# LMP91000_NO2_Sensor.net
KiCad netlist of a schematic drawn in Altium Designer
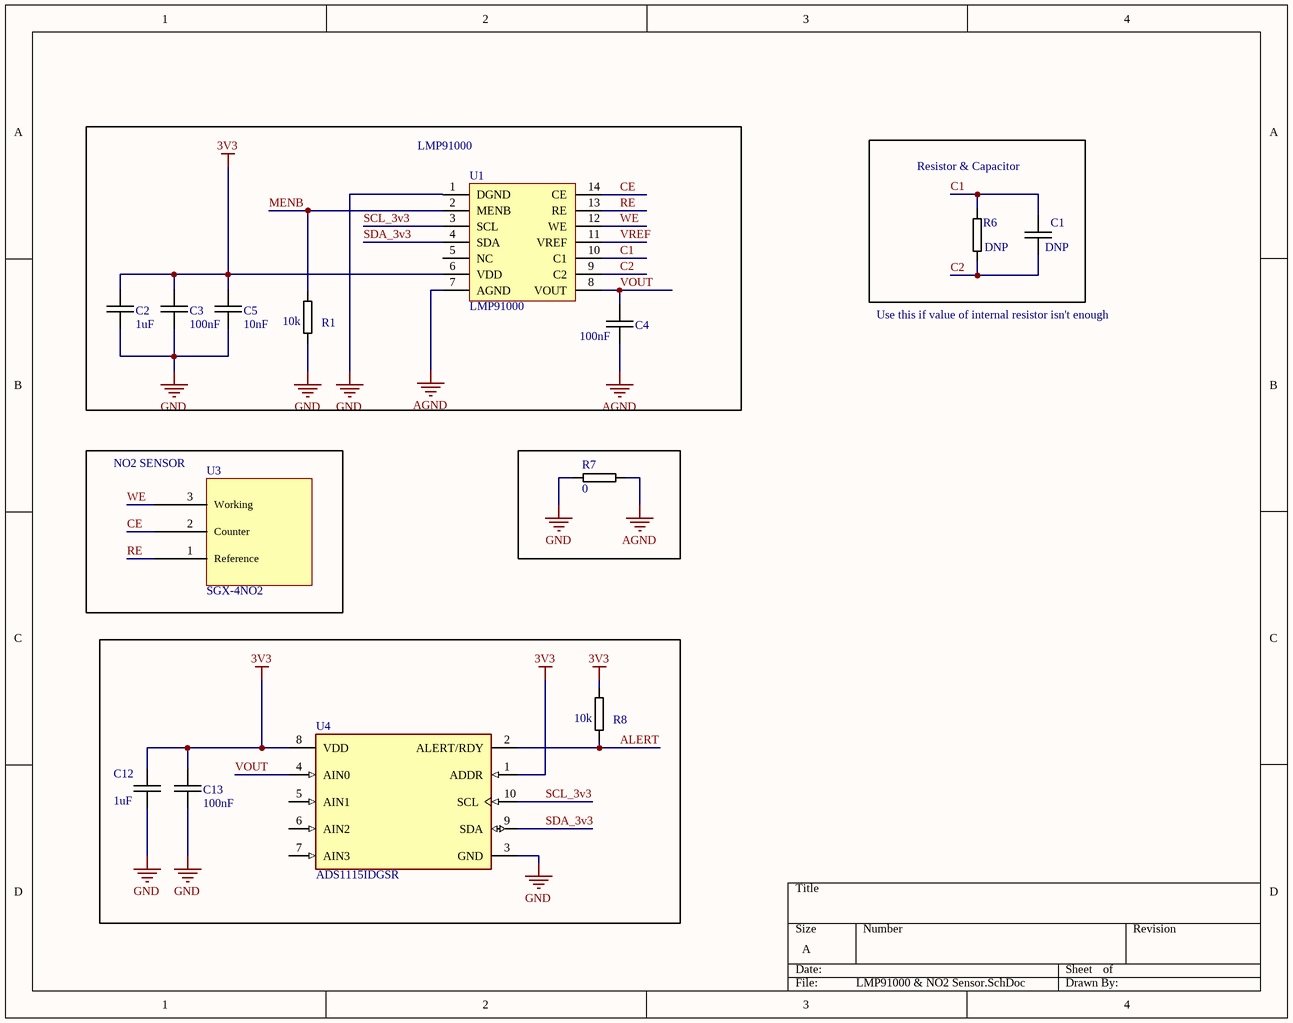
[diagram p0: LMP91000 & NO2 Sensor.SchDoc]

(export (version "E")
  (design (tool "Eeschema 10.0.6"))
  (components
    (comp (ref "C1") (value "DNP") (footprint "0603C") (libsource (lib "TAVU Altium library") (part "0603C")))
    (comp (ref "C2") (value "1uF") (footprint "0603C") (libsource (lib "TAVU Altium library") (part "0603C")))
    (comp (ref "C3")
      (value "100nF")
      (footprint "0603C")
      (libsource (lib "TAVU Altium library") (part "0603C"))
    )
    (comp (ref "C4")
      (value "100nF")
      (footprint "0603C")
      (libsource (lib "TAVU Altium library") (part "0603C"))
    )
    (comp (ref "C5")
      (value "10nF")
      (footprint "0603C")
      (libsource (lib "TAVU Altium library") (part "0603C"))
    )
    (comp (ref "C12")
      (value "1uF")
      (footprint "0603C")
      (libsource (lib "TAVU Altium library") (part "0603C"))
    )
    (comp (ref "C13")
      (value "100nF")
      (footprint "0603C")
      (libsource (lib "TAVU Altium library") (part "0603C"))
    )
    (comp (ref "R1") (value "10k") (footprint "0603R") (libsource (lib "TAVU Altium library") (part "0603R")))
    (comp (ref "R6") (value "DNP") (footprint "0603R") (libsource (lib "TAVU Altium library") (part "0603R")))
    (comp (ref "R7") (value "0") (footprint "0603R") (libsource (lib "TAVU Altium library") (part "0603R")))
    (comp (ref "R8") (value "10k") (footprint "0603R") (libsource (lib "TAVU Altium library") (part "0603R")))
    (comp (ref "U1")
      (value "LMP91000")
      (footprint "LMP91000")
      (libsource (lib "TAVU Altium library") (part "LMP91000"))
    )
    (comp (ref "U3")
      (value "SGX-4NO2")
      (footprint "SGX-4NO2")
      (libsource (lib "TAVU Altium library") (part "SGX-4NO2"))
    )
    (comp (ref "U4")
      (value "ADS1115IDGSR")
      (footprint "FP-DGS0010A-MFG")
      (description "IC ADC 16BIT SIGMA-DELTA 10VSSOP")
      (libsource (lib "Altium Content Vault") (part "1442cd67780685bba1a77ae27c88037"))
    )
  )
  (nets
    (net (code "1") (name "/ALERT") (class "Default")
      (node (ref "R8") (pin "1") (pinfunction "1_1") (pintype "passive"))
      (node (ref "U4") (pin "2") (pinfunction "ALERT/RDY_2") (pintype "open_collector"))
    )
    (net (code "2") (name "/C1") (class "Default")
      (node (ref "C1") (pin "2") (pinfunction "2_2") (pintype "passive"))
      (node (ref "R6") (pin "2") (pinfunction "2_2") (pintype "passive"))
      (node (ref "U1") (pin "10") (pinfunction "C1_10") (pintype "passive"))
    )
    (net (code "3") (name "/C2") (class "Default")
      (node (ref "C1") (pin "1") (pinfunction "1_1") (pintype "passive"))
      (node (ref "R6") (pin "1") (pinfunction "1_1") (pintype "passive"))
      (node (ref "U1") (pin "9") (pinfunction "C2_9") (pintype "passive"))
    )
    (net (code "4") (name "/CE") (class "Default")
      (node (ref "U1") (pin "14") (pinfunction "CE_14") (pintype "passive"))
      (node (ref "U3") (pin "2") (pinfunction "Counter_2") (pintype "passive"))
    )
    (net (code "5") (name "/MENB") (class "Default")
      (node (ref "R1") (pin "2") (pinfunction "2_2") (pintype "passive"))
      (node (ref "U1") (pin "2") (pinfunction "MENB_2") (pintype "passive"))
    )
    (net (code "6") (name "/RE") (class "Default")
      (node (ref "U1") (pin "13") (pinfunction "RE_13") (pintype "passive"))
      (node (ref "U3") (pin "1") (pinfunction "Reference_1") (pintype "passive"))
    )
    (net (code "7") (name "/SCL_3v3") (class "Default")
      (node (ref "U1") (pin "3") (pinfunction "SCL_3") (pintype "passive"))
      (node (ref "U4") (pin "10") (pinfunction "SCL_10") (pintype "input"))
    )
    (net (code "8") (name "/SDA_3v3") (class "Default")
      (node (ref "U1") (pin "4") (pinfunction "SDA_4") (pintype "passive"))
      (node (ref "U4") (pin "9") (pinfunction "SDA_9") (pintype "bidirectional"))
    )
    (net (code "9") (name "/VOUT") (class "Default")
      (node (ref "C4") (pin "2") (pinfunction "2_2") (pintype "passive"))
      (node (ref "U1") (pin "8") (pinfunction "VOUT_8") (pintype "passive"))
      (node (ref "U4") (pin "4") (pinfunction "AIN0_4") (pintype "input"))
    )
    (net (code "10") (name "/VREF") (class "Default")
      (node (ref "U1") (pin "11") (pinfunction "VREF_11") (pintype "passive"))
    )
    (net (code "11") (name "/WE") (class "Default")
      (node (ref "U1") (pin "12") (pinfunction "WE_12") (pintype "passive"))
      (node (ref "U3") (pin "3") (pinfunction "Working_3") (pintype "passive"))
    )
    (net (code "12") (name "3V3") (class "Default")
      (node (ref "C12") (pin "2") (pinfunction "2_2") (pintype "passive"))
      (node (ref "C13") (pin "2") (pinfunction "2_2") (pintype "passive"))
      (node (ref "C2") (pin "1") (pinfunction "1_1") (pintype "passive"))
      (node (ref "C3") (pin "1") (pinfunction "1_1") (pintype "passive"))
      (node (ref "C5") (pin "1") (pinfunction "1_1") (pintype "passive"))
      (node (ref "R8") (pin "2") (pinfunction "2_2") (pintype "passive"))
      (node (ref "U1") (pin "6") (pinfunction "VDD_6") (pintype "passive"))
      (node (ref "U4") (pin "1") (pinfunction "ADDR_1") (pintype "input"))
      (node (ref "U4") (pin "8") (pinfunction "VDD_8") (pintype "power_in"))
    )
    (net (code "13") (name "AGND") (class "Default")
      (node (ref "C4") (pin "1") (pinfunction "1_1") (pintype "passive"))
      (node (ref "R7") (pin "1") (pinfunction "1_1") (pintype "passive"))
      (node (ref "U1") (pin "7") (pinfunction "AGND_7") (pintype "passive"))
    )
    (net (code "14") (name "GND") (class "Default")
      (node (ref "C12") (pin "1") (pinfunction "1_1") (pintype "passive"))
      (node (ref "C13") (pin "1") (pinfunction "1_1") (pintype "passive"))
      (node (ref "C2") (pin "2") (pinfunction "2_2") (pintype "passive"))
      (node (ref "C3") (pin "2") (pinfunction "2_2") (pintype "passive"))
      (node (ref "C5") (pin "2") (pinfunction "2_2") (pintype "passive"))
      (node (ref "R1") (pin "1") (pinfunction "1_1") (pintype "passive"))
      (node (ref "R7") (pin "2") (pinfunction "2_2") (pintype "passive"))
      (node (ref "U1") (pin "1") (pinfunction "DGND_1") (pintype "passive"))
      (node (ref "U4") (pin "3") (pinfunction "GND_3") (pintype "power_in"))
    )
    (net (code "15") (name "unconnected-(U1-NC-Pad5)") (class "Default")
      (node (ref "U1") (pin "5") (pinfunction "NC_5") (pintype "passive"))
    )
    (net (code "16") (name "unconnected-(U4-AIN1-Pad5)") (class "Default")
      (node (ref "U4") (pin "5") (pinfunction "AIN1_5") (pintype "input"))
    )
    (net (code "17") (name "unconnected-(U4-AIN2-Pad6)") (class "Default")
      (node (ref "U4") (pin "6") (pinfunction "AIN2_6") (pintype "input"))
    )
    (net (code "18") (name "unconnected-(U4-AIN3-Pad7)") (class "Default")
      (node (ref "U4") (pin "7") (pinfunction "AIN3_7") (pintype "input"))
    )
  )
)
